# PcbBox_Demonstateur.net
KiCad netlist of a schematic drawn in Altium Designer
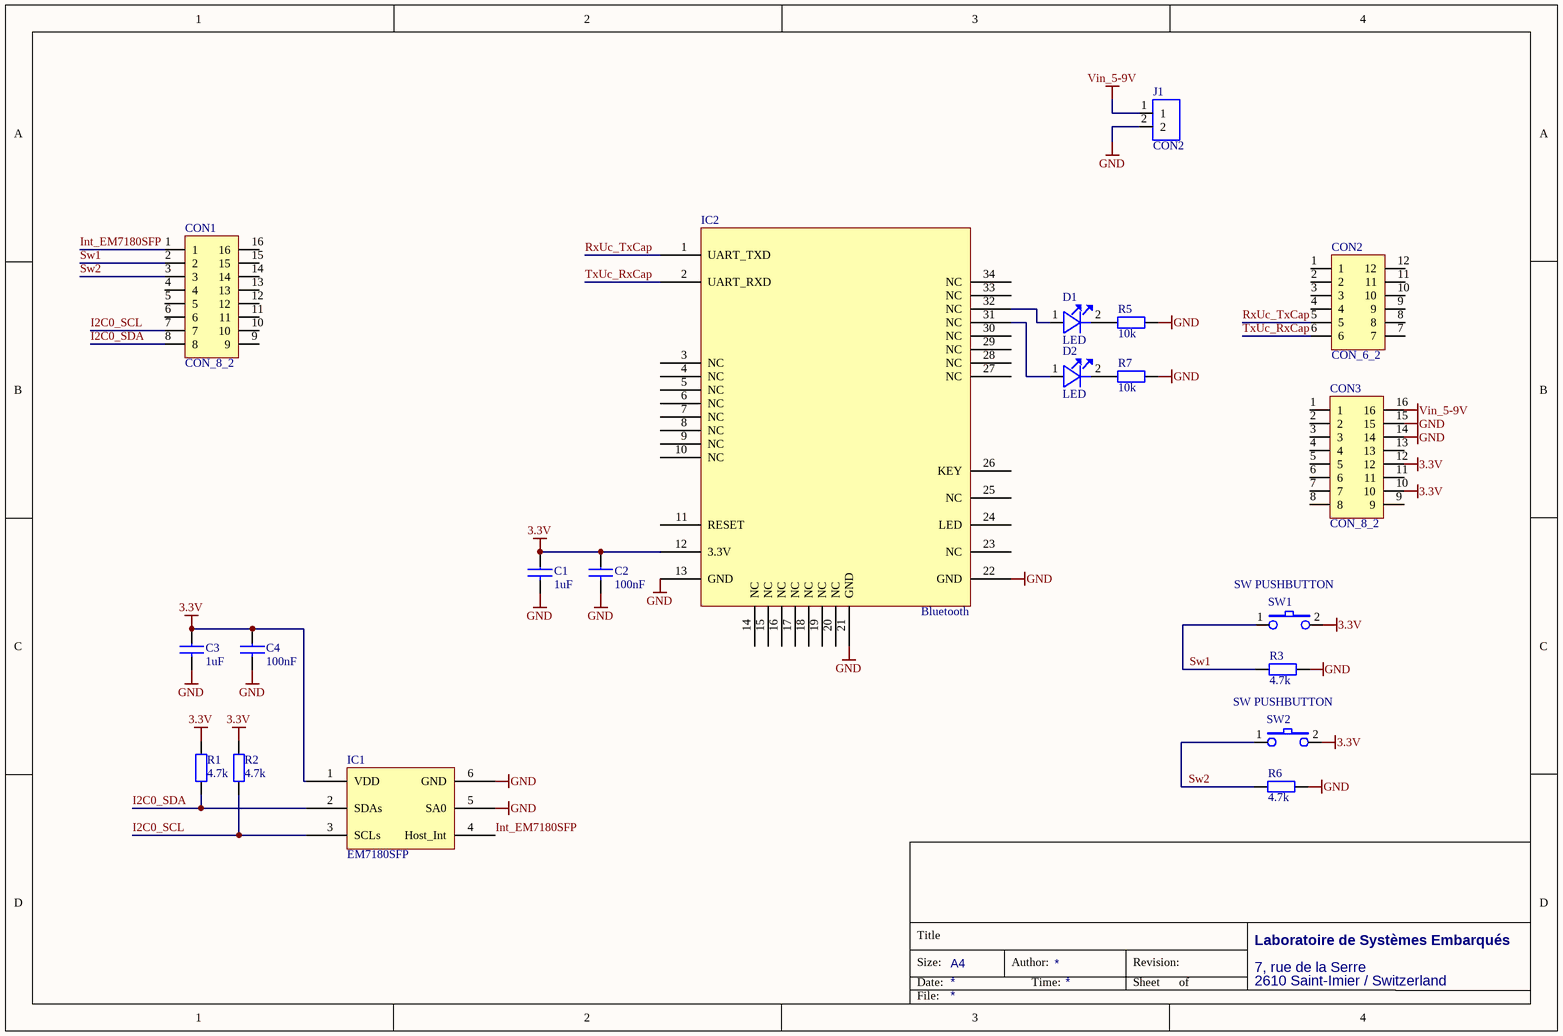
[diagram p0: PcbBox_Demonstateur.SchDoc]

(export (version "E")
  (design (tool "Eeschema 10.0.6"))
  (components
    (comp (ref "C1")
      (value "1uF")
      (footprint "080503")
      (description "Condo céramique")
      (libsource (lib "EISI") (part "CAPA"))
    )
    (comp (ref "C2")
      (value "100nF")
      (footprint "080503")
      (description "Condo céramique")
      (libsource (lib "EISI") (part "CAPA"))
    )
    (comp (ref "C3")
      (value "1uF")
      (footprint "080503")
      (description "Condo céramique")
      (libsource (lib "EISI") (part "CAPA"))
    )
    (comp (ref "C4")
      (value "100nF")
      (footprint "080503")
      (description "Condo céramique")
      (libsource (lib "EISI") (part "CAPA"))
    )
    (comp (ref "CON1")
      (value "CON_8_2")
      (footprint "J208")
      (libsource (lib "Smartstick_Quaternions") (part "CON_8_2"))
    )
    (comp (ref "CON2")
      (value "CON_6_2")
      (footprint "j206")
      (libsource (lib "Smartstick_Quaternions") (part "CON_6_2"))
    )
    (comp (ref "CON3")
      (value "CON_8_2")
      (footprint "J208")
      (libsource (lib "Smartstick_Quaternions") (part "CON_8_2"))
    )
    (comp (ref "D1")
      (value "LED")
      (footprint "0805_Led")
      (description "Led")
      (libsource (lib "EISI") (part "LED"))
    )
    (comp (ref "D2")
      (value "LED")
      (footprint "0805_Led")
      (description "Led")
      (libsource (lib "EISI") (part "LED"))
    )
    (comp (ref "IC1")
      (value "EM7180SFP")
      (footprint "Footprint_EM7180")
      (libsource (lib "Smartstick_Quaternions") (part "EM7180SFP"))
    )
    (comp (ref "IC2")
      (value "Bluetooth")
      (footprint "BT HC-05")
      (libsource (lib "Smartstick_Quaternions") (part "SEEDSTUDIO_HC-05"))
    )
    (comp (ref "J1")
      (value "CON2")
      (footprint "J201")
      (description "Con2")
      (libsource (lib "EISI") (part "CON2"))
    )
    (comp (ref "R1")
      (value "4.7k")
      (footprint "080501")
      (description "Resistance")
      (fields (field (name "Comment") "RES"))
      (libsource (lib "") (part "RES_1"))
    )
    (comp (ref "R2")
      (value "4.7k")
      (footprint "080501")
      (description "Resistance")
      (fields (field (name "Comment") "RES"))
      (libsource (lib "") (part "RES_1"))
    )
    (comp (ref "R3")
      (value "4.7k")
      (footprint "080501")
      (description "Resistance")
      (fields (field (name "Comment") "RES"))
      (libsource (lib "EISI") (part "RES"))
    )
    (comp (ref "R5")
      (value "10k")
      (footprint "080501")
      (description "Resistance")
      (fields (field (name "Comment") "RES"))
      (libsource (lib "EISI") (part "RES"))
    )
    (comp (ref "R6")
      (value "4.7k")
      (footprint "080501")
      (description "Resistance")
      (fields (field (name "Comment") "RES"))
      (libsource (lib "EISI") (part "RES"))
    )
    (comp (ref "R7")
      (value "10k")
      (footprint "080501")
      (description "Resistance")
      (fields (field (name "Comment") "RES"))
      (libsource (lib "EISI") (part "RES"))
    )
    (comp (ref "SW1")
      (value "SW PUSHBUTTON")
      (footprint "BoutonPoussoir")
      (libsource (lib "EISI") (part "SW PUSHBUTTON"))
    )
    (comp (ref "SW2")
      (value "SW PUSHBUTTON")
      (footprint "BoutonPoussoir")
      (libsource (lib "EISI") (part "SW PUSHBUTTON"))
    )
  )
  (nets
    (net (code "1") (name "/I2C0_SCL") (class "Default")
      (node (ref "CON1") (pin "7") (pinfunction "7_7") (pintype "passive"))
      (node (ref "IC1") (pin "3") (pinfunction "SCLs_3") (pintype "passive"))
      (node (ref "R2") (pin "2") (pinfunction "2_2") (pintype "passive"))
    )
    (net (code "2") (name "/I2C0_SDA") (class "Default")
      (node (ref "CON1") (pin "8") (pinfunction "8_8") (pintype "passive"))
      (node (ref "IC1") (pin "2") (pinfunction "SDAs_2") (pintype "passive"))
      (node (ref "R1") (pin "2") (pinfunction "2_2") (pintype "passive"))
    )
    (net (code "3") (name "/Int_EM7180SFP") (class "Default")
      (node (ref "CON1") (pin "1") (pinfunction "1_1") (pintype "passive"))
      (node (ref "IC1") (pin "4") (pinfunction "Host_Int_4") (pintype "passive"))
    )
    (net (code "4") (name "/RxUc_TxCap") (class "Default")
      (node (ref "CON2") (pin "5") (pinfunction "5_5") (pintype "passive"))
      (node (ref "IC2") (pin "1") (pinfunction "UART_TXD_1") (pintype "passive"))
    )
    (net (code "5") (name "/Sw1") (class "Default")
      (node (ref "CON1") (pin "2") (pinfunction "2_2") (pintype "passive"))
      (node (ref "R3") (pin "1") (pinfunction "1_1") (pintype "passive"))
      (node (ref "SW1") (pin "1") (pinfunction "1_1") (pintype "passive"))
    )
    (net (code "6") (name "/Sw2") (class "Default")
      (node (ref "CON1") (pin "3") (pinfunction "3_3") (pintype "passive"))
      (node (ref "R6") (pin "1") (pinfunction "1_1") (pintype "passive"))
      (node (ref "SW2") (pin "1") (pinfunction "1_1") (pintype "passive"))
    )
    (net (code "7") (name "/TxUc_RxCap") (class "Default")
      (node (ref "CON2") (pin "6") (pinfunction "6_6") (pintype "passive"))
      (node (ref "IC2") (pin "2") (pinfunction "UART_RXD_2") (pintype "passive"))
    )
    (net (code "8") (name "3.3V") (class "Default")
      (node (ref "C1") (pin "1") (pinfunction "1_1") (pintype "passive"))
      (node (ref "C2") (pin "1") (pinfunction "1_1") (pintype "passive"))
      (node (ref "C3") (pin "1") (pinfunction "1_1") (pintype "passive"))
      (node (ref "C4") (pin "1") (pinfunction "1_1") (pintype "passive"))
      (node (ref "CON3") (pin "10") (pinfunction "10_10") (pintype "passive"))
      (node (ref "CON3") (pin "12") (pinfunction "12_12") (pintype "passive"))
      (node (ref "IC1") (pin "1") (pinfunction "VDD_1") (pintype "passive"))
      (node (ref "IC2") (pin "12") (pinfunction "3.3V_12") (pintype "passive"))
      (node (ref "R1") (pin "1") (pinfunction "1_1") (pintype "passive"))
      (node (ref "R2") (pin "1") (pinfunction "1_1") (pintype "passive"))
      (node (ref "SW1") (pin "2") (pinfunction "2_2") (pintype "passive"))
      (node (ref "SW2") (pin "2") (pinfunction "2_2") (pintype "passive"))
    )
    (net (code "9") (name "GND") (class "Default")
      (node (ref "C1") (pin "2") (pinfunction "2_2") (pintype "passive"))
      (node (ref "C2") (pin "2") (pinfunction "2_2") (pintype "passive"))
      (node (ref "C3") (pin "2") (pinfunction "2_2") (pintype "passive"))
      (node (ref "C4") (pin "2") (pinfunction "2_2") (pintype "passive"))
      (node (ref "CON3") (pin "14") (pinfunction "14_14") (pintype "passive"))
      (node (ref "CON3") (pin "15") (pinfunction "15_15") (pintype "passive"))
      (node (ref "IC1") (pin "5") (pinfunction "SA0_5") (pintype "passive"))
      (node (ref "IC1") (pin "6") (pinfunction "GND_6") (pintype "passive"))
      (node (ref "IC2") (pin "13") (pinfunction "GND_13") (pintype "passive"))
      (node (ref "IC2") (pin "21") (pinfunction "GND_21") (pintype "passive"))
      (node (ref "IC2") (pin "22") (pinfunction "GND_22") (pintype "passive"))
      (node (ref "J1") (pin "2") (pinfunction "2_2") (pintype "passive"))
      (node (ref "R3") (pin "2") (pinfunction "2_2") (pintype "passive"))
      (node (ref "R5") (pin "2") (pinfunction "2_2") (pintype "passive"))
      (node (ref "R6") (pin "2") (pinfunction "2_2") (pintype "passive"))
      (node (ref "R7") (pin "2") (pinfunction "2_2") (pintype "passive"))
    )
    (net (code "10") (name "Net-(D1-AN)") (class "Default")
      (node (ref "D1") (pin "1") (pinfunction "AN_1") (pintype "passive"))
      (node (ref "IC2") (pin "32") (pinfunction "NC_32") (pintype "passive"))
    )
    (net (code "11") (name "Net-(D1-CAT)") (class "Default")
      (node (ref "D1") (pin "2") (pinfunction "CAT_2") (pintype "passive"))
      (node (ref "R5") (pin "1") (pinfunction "1_1") (pintype "passive"))
    )
    (net (code "12") (name "Net-(D2-AN)") (class "Default")
      (node (ref "D2") (pin "1") (pinfunction "AN_1") (pintype "passive"))
      (node (ref "IC2") (pin "31") (pinfunction "NC_31") (pintype "passive"))
    )
    (net (code "13") (name "Net-(D2-CAT)") (class "Default")
      (node (ref "D2") (pin "2") (pinfunction "CAT_2") (pintype "passive"))
      (node (ref "R7") (pin "1") (pinfunction "1_1") (pintype "passive"))
    )
    (net (code "14") (name "Vin_5-9V") (class "Default")
      (node (ref "CON3") (pin "16") (pinfunction "16_16") (pintype "passive"))
      (node (ref "J1") (pin "1") (pinfunction "1_1") (pintype "passive"))
    )
    (net (code "15") (name "unconnected-(CON1-Pad4)") (class "Default")
      (node (ref "CON1") (pin "4") (pinfunction "4_4") (pintype "passive"))
    )
    (net (code "16") (name "unconnected-(CON1-Pad5)") (class "Default")
      (node (ref "CON1") (pin "5") (pinfunction "5_5") (pintype "passive"))
    )
    (net (code "17") (name "unconnected-(CON1-Pad6)") (class "Default")
      (node (ref "CON1") (pin "6") (pinfunction "6_6") (pintype "passive"))
    )
    (net (code "18") (name "unconnected-(CON1-Pad9)") (class "Default")
      (node (ref "CON1") (pin "9") (pinfunction "9_9") (pintype "passive"))
    )
    (net (code "19") (name "unconnected-(CON1-Pad10)") (class "Default")
      (node (ref "CON1") (pin "10") (pinfunction "10_10") (pintype "passive"))
    )
    (net (code "20") (name "unconnected-(CON1-Pad11)") (class "Default")
      (node (ref "CON1") (pin "11") (pinfunction "11_11") (pintype "passive"))
    )
    (net (code "21") (name "unconnected-(CON1-Pad12)") (class "Default")
      (node (ref "CON1") (pin "12") (pinfunction "12_12") (pintype "passive"))
    )
    (net (code "22") (name "unconnected-(CON1-Pad13)") (class "Default")
      (node (ref "CON1") (pin "13") (pinfunction "13_13") (pintype "passive"))
    )
    (net (code "23") (name "unconnected-(CON1-Pad14)") (class "Default")
      (node (ref "CON1") (pin "14") (pinfunction "14_14") (pintype "passive"))
    )
    (net (code "24") (name "unconnected-(CON1-Pad15)") (class "Default")
      (node (ref "CON1") (pin "15") (pinfunction "15_15") (pintype "passive"))
    )
    (net (code "25") (name "unconnected-(CON1-Pad16)") (class "Default")
      (node (ref "CON1") (pin "16") (pinfunction "16_16") (pintype "passive"))
    )
    (net (code "26") (name "unconnected-(CON2-Pad1)") (class "Default")
      (node (ref "CON2") (pin "1") (pinfunction "1_1") (pintype "passive"))
    )
    (net (code "27") (name "unconnected-(CON2-Pad2)") (class "Default")
      (node (ref "CON2") (pin "2") (pinfunction "2_2") (pintype "passive"))
    )
    (net (code "28") (name "unconnected-(CON2-Pad3)") (class "Default")
      (node (ref "CON2") (pin "3") (pinfunction "3_3") (pintype "passive"))
    )
    (net (code "29") (name "unconnected-(CON2-Pad4)") (class "Default")
      (node (ref "CON2") (pin "4") (pinfunction "4_4") (pintype "passive"))
    )
    (net (code "30") (name "unconnected-(CON2-Pad7)") (class "Default")
      (node (ref "CON2") (pin "7") (pinfunction "7_7") (pintype "passive"))
    )
    (net (code "31") (name "unconnected-(CON2-Pad8)") (class "Default")
      (node (ref "CON2") (pin "8") (pinfunction "8_8") (pintype "passive"))
    )
    (net (code "32") (name "unconnected-(CON2-Pad9)") (class "Default")
      (node (ref "CON2") (pin "9") (pinfunction "9_9") (pintype "passive"))
    )
    (net (code "33") (name "unconnected-(CON2-Pad10)") (class "Default")
      (node (ref "CON2") (pin "10") (pinfunction "10_10") (pintype "passive"))
    )
    (net (code "34") (name "unconnected-(CON2-Pad11)") (class "Default")
      (node (ref "CON2") (pin "11") (pinfunction "11_11") (pintype "passive"))
    )
    (net (code "35") (name "unconnected-(CON2-Pad12)") (class "Default")
      (node (ref "CON2") (pin "12") (pinfunction "12_12") (pintype "passive"))
    )
    (net (code "36") (name "unconnected-(CON3-Pad1)") (class "Default")
      (node (ref "CON3") (pin "1") (pinfunction "1_1") (pintype "passive"))
    )
    (net (code "37") (name "unconnected-(CON3-Pad2)") (class "Default")
      (node (ref "CON3") (pin "2") (pinfunction "2_2") (pintype "passive"))
    )
    (net (code "38") (name "unconnected-(CON3-Pad3)") (class "Default")
      (node (ref "CON3") (pin "3") (pinfunction "3_3") (pintype "passive"))
    )
    (net (code "39") (name "unconnected-(CON3-Pad4)") (class "Default")
      (node (ref "CON3") (pin "4") (pinfunction "4_4") (pintype "passive"))
    )
    (net (code "40") (name "unconnected-(CON3-Pad5)") (class "Default")
      (node (ref "CON3") (pin "5") (pinfunction "5_5") (pintype "passive"))
    )
    (net (code "41") (name "unconnected-(CON3-Pad6)") (class "Default")
      (node (ref "CON3") (pin "6") (pinfunction "6_6") (pintype "passive"))
    )
    (net (code "42") (name "unconnected-(CON3-Pad7)") (class "Default")
      (node (ref "CON3") (pin "7") (pinfunction "7_7") (pintype "passive"))
    )
    (net (code "43") (name "unconnected-(CON3-Pad8)") (class "Default")
      (node (ref "CON3") (pin "8") (pinfunction "8_8") (pintype "passive"))
    )
    (net (code "44") (name "unconnected-(CON3-Pad9)") (class "Default")
      (node (ref "CON3") (pin "9") (pinfunction "9_9") (pintype "passive"))
    )
    (net (code "45") (name "unconnected-(CON3-Pad11)") (class "Default")
      (node (ref "CON3") (pin "11") (pinfunction "11_11") (pintype "passive"))
    )
    (net (code "46") (name "unconnected-(CON3-Pad13)") (class "Default")
      (node (ref "CON3") (pin "13") (pinfunction "13_13") (pintype "passive"))
    )
    (net (code "47") (name "unconnected-(IC2-KEY-Pad26)") (class "Default")
      (node (ref "IC2") (pin "26") (pinfunction "KEY_26") (pintype "passive"))
    )
    (net (code "48") (name "unconnected-(IC2-LED-Pad24)") (class "Default")
      (node (ref "IC2") (pin "24") (pinfunction "LED_24") (pintype "passive"))
    )
    (net (code "49") (name "unconnected-(IC2-NC-Pad3)") (class "Default")
      (node (ref "IC2") (pin "3") (pinfunction "NC_3") (pintype "passive"))
    )
    (net (code "50") (name "unconnected-(IC2-NC-Pad4)") (class "Default")
      (node (ref "IC2") (pin "4") (pinfunction "NC_4") (pintype "passive"))
    )
    (net (code "51") (name "unconnected-(IC2-NC-Pad5)") (class "Default")
      (node (ref "IC2") (pin "5") (pinfunction "NC_5") (pintype "passive"))
    )
    (net (code "52") (name "unconnected-(IC2-NC-Pad6)") (class "Default")
      (node (ref "IC2") (pin "6") (pinfunction "NC_6") (pintype "passive"))
    )
    (net (code "53") (name "unconnected-(IC2-NC-Pad7)") (class "Default")
      (node (ref "IC2") (pin "7") (pinfunction "NC_7") (pintype "passive"))
    )
    (net (code "54") (name "unconnected-(IC2-NC-Pad8)") (class "Default")
      (node (ref "IC2") (pin "8") (pinfunction "NC_8") (pintype "passive"))
    )
    (net (code "55") (name "unconnected-(IC2-NC-Pad9)") (class "Default")
      (node (ref "IC2") (pin "9") (pinfunction "NC_9") (pintype "passive"))
    )
    (net (code "56") (name "unconnected-(IC2-NC-Pad10)") (class "Default")
      (node (ref "IC2") (pin "10") (pinfunction "NC_10") (pintype "passive"))
    )
    (net (code "57") (name "unconnected-(IC2-NC-Pad14)") (class "Default")
      (node (ref "IC2") (pin "14") (pinfunction "NC_14") (pintype "passive"))
    )
    (net (code "58") (name "unconnected-(IC2-NC-Pad15)") (class "Default")
      (node (ref "IC2") (pin "15") (pinfunction "NC_15") (pintype "passive"))
    )
    (net (code "59") (name "unconnected-(IC2-NC-Pad16)") (class "Default")
      (node (ref "IC2") (pin "16") (pinfunction "NC_16") (pintype "passive"))
    )
    (net (code "60") (name "unconnected-(IC2-NC-Pad17)") (class "Default")
      (node (ref "IC2") (pin "17") (pinfunction "NC_17") (pintype "passive"))
    )
    (net (code "61") (name "unconnected-(IC2-NC-Pad18)") (class "Default")
      (node (ref "IC2") (pin "18") (pinfunction "NC_18") (pintype "passive"))
    )
    (net (code "62") (name "unconnected-(IC2-NC-Pad19)") (class "Default")
      (node (ref "IC2") (pin "19") (pinfunction "NC_19") (pintype "passive"))
    )
    (net (code "63") (name "unconnected-(IC2-NC-Pad20)") (class "Default")
      (node (ref "IC2") (pin "20") (pinfunction "NC_20") (pintype "passive"))
    )
    (net (code "64") (name "unconnected-(IC2-NC-Pad23)") (class "Default")
      (node (ref "IC2") (pin "23") (pinfunction "NC_23") (pintype "passive"))
    )
    (net (code "65") (name "unconnected-(IC2-NC-Pad25)") (class "Default")
      (node (ref "IC2") (pin "25") (pinfunction "NC_25") (pintype "passive"))
    )
    (net (code "66") (name "unconnected-(IC2-NC-Pad27)") (class "Default")
      (node (ref "IC2") (pin "27") (pinfunction "NC_27") (pintype "passive"))
    )
    (net (code "67") (name "unconnected-(IC2-NC-Pad28)") (class "Default")
      (node (ref "IC2") (pin "28") (pinfunction "NC_28") (pintype "passive"))
    )
    (net (code "68") (name "unconnected-(IC2-NC-Pad29)") (class "Default")
      (node (ref "IC2") (pin "29") (pinfunction "NC_29") (pintype "passive"))
    )
    (net (code "69") (name "unconnected-(IC2-NC-Pad30)") (class "Default")
      (node (ref "IC2") (pin "30") (pinfunction "NC_30") (pintype "passive"))
    )
    (net (code "70") (name "unconnected-(IC2-NC-Pad33)") (class "Default")
      (node (ref "IC2") (pin "33") (pinfunction "NC_33") (pintype "passive"))
    )
    (net (code "71") (name "unconnected-(IC2-NC-Pad34)") (class "Default")
      (node (ref "IC2") (pin "34") (pinfunction "NC_34") (pintype "passive"))
    )
    (net (code "72") (name "unconnected-(IC2-RESET-Pad11)") (class "Default")
      (node (ref "IC2") (pin "11") (pinfunction "RESET_11") (pintype "passive"))
    )
  )
)
